# controller.net
KiCad netlist of a schematic drawn in Altium Designer
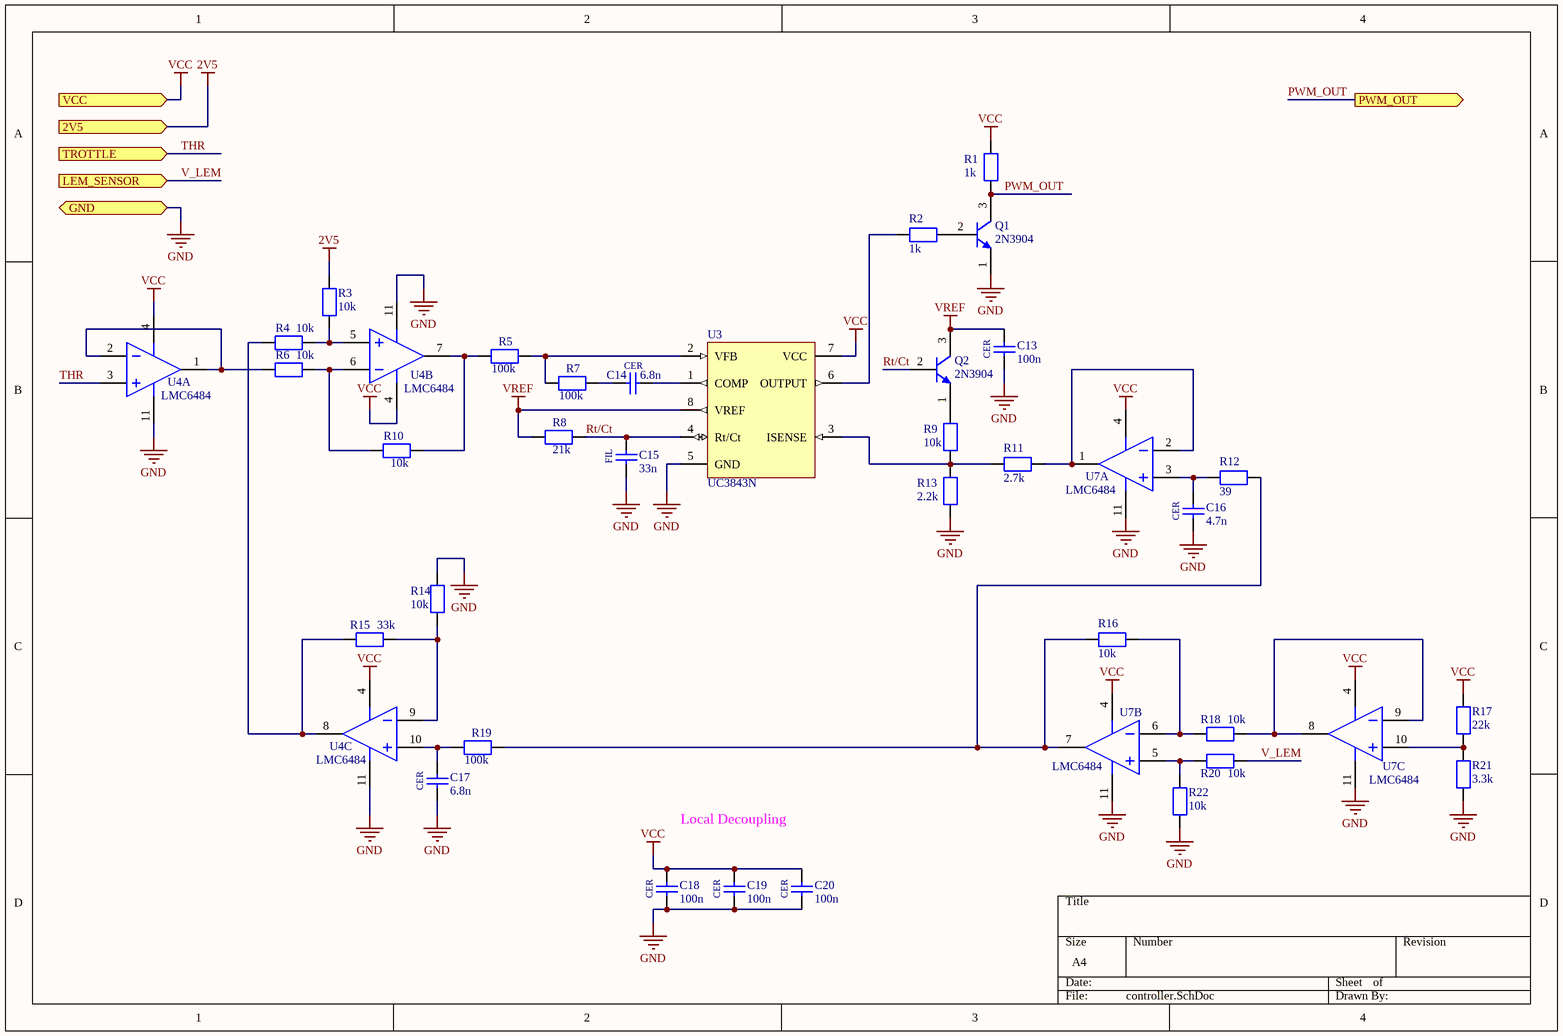
[diagram p0: controller.SchDoc]

(export (version "E")
  (design (tool "Eeschema 10.0.6"))
  (components
    (comp (ref "C13") (value "100n") (footprint "CAP_CER_2.50") (libsource (lib "go_kart") (part "CAP_CER")))
    (comp (ref "C14") (value "6.8n") (footprint "CAP_CER_2.50") (libsource (lib "go_kart") (part "CAP_CER")))
    (comp (ref "C15") (value "33n") (footprint "CAP_FILM_10.0") (libsource (lib "go_kart") (part "CAP_FILM")))
    (comp (ref "C16") (value "4.7n") (footprint "CAP_CER_2.50") (libsource (lib "go_kart") (part "CAP_CER")))
    (comp (ref "C17") (value "6.8n") (footprint "CAP_CER_2.50") (libsource (lib "go_kart") (part "CAP_CER")))
    (comp (ref "C18") (value "100n") (footprint "CAP_CER_2.50") (libsource (lib "go_kart") (part "CAP_CER")))
    (comp (ref "C19") (value "100n") (footprint "CAP_CER_2.50") (libsource (lib "go_kart") (part "CAP_CER")))
    (comp (ref "C20") (value "100n") (footprint "CAP_CER_2.50") (libsource (lib "go_kart") (part "CAP_CER")))
    (comp (ref "Q1")
      (value "2N3904")
      (footprint "ONSC-TO-92-3-29-04_AD")
      (libsource (lib "go_kart") (part "2N3904"))
    )
    (comp (ref "Q2")
      (value "2N3904")
      (footprint "ONSC-TO-92-3-29-04_AD")
      (libsource (lib "go_kart") (part "2N3904"))
    )
    (comp (ref "R1")
      (value "1k")
      (footprint "RESISTOR_THROUGH_HOLE")
      (libsource (lib "go_kart") (part "Resistor"))
    )
    (comp (ref "R2")
      (value "1k")
      (footprint "RESISTOR_THROUGH_HOLE")
      (libsource (lib "go_kart") (part "Resistor"))
    )
    (comp (ref "R3")
      (value "10k")
      (footprint "RESISTOR_THROUGH_HOLE")
      (libsource (lib "go_kart") (part "Resistor"))
    )
    (comp (ref "R4")
      (value "10k")
      (footprint "RESISTOR_THROUGH_HOLE")
      (libsource (lib "go_kart") (part "Resistor"))
    )
    (comp (ref "R5")
      (value "100k")
      (footprint "RESISTOR_THROUGH_HOLE")
      (libsource (lib "go_kart") (part "Resistor"))
    )
    (comp (ref "R6")
      (value "10k")
      (footprint "RESISTOR_THROUGH_HOLE")
      (libsource (lib "go_kart") (part "Resistor"))
    )
    (comp (ref "R7")
      (value "100k")
      (footprint "RESISTOR_THROUGH_HOLE")
      (libsource (lib "go_kart") (part "Resistor"))
    )
    (comp (ref "R8")
      (value "21k")
      (footprint "RESISTOR_THROUGH_HOLE")
      (libsource (lib "go_kart") (part "Resistor"))
    )
    (comp (ref "R9")
      (value "10k")
      (footprint "RESISTOR_THROUGH_HOLE")
      (libsource (lib "go_kart") (part "Resistor"))
    )
    (comp (ref "R10")
      (value "10k")
      (footprint "RESISTOR_THROUGH_HOLE")
      (libsource (lib "go_kart") (part "Resistor"))
    )
    (comp (ref "R11")
      (value "2.7k")
      (footprint "RESISTOR_THROUGH_HOLE")
      (libsource (lib "go_kart") (part "Resistor"))
    )
    (comp (ref "R12")
      (value "39")
      (footprint "RESISTOR_THROUGH_HOLE")
      (libsource (lib "go_kart") (part "Resistor"))
    )
    (comp (ref "R13")
      (value "2.2k")
      (footprint "RESISTOR_THROUGH_HOLE")
      (libsource (lib "go_kart") (part "Resistor"))
    )
    (comp (ref "R14")
      (value "10k")
      (footprint "RESISTOR_THROUGH_HOLE")
      (libsource (lib "go_kart") (part "Resistor"))
    )
    (comp (ref "R15")
      (value "33k")
      (footprint "RESISTOR_THROUGH_HOLE")
      (libsource (lib "go_kart") (part "Resistor"))
    )
    (comp (ref "R16")
      (value "10k")
      (footprint "RESISTOR_THROUGH_HOLE")
      (libsource (lib "go_kart") (part "Resistor"))
    )
    (comp (ref "R17")
      (value "22k")
      (footprint "RESISTOR_THROUGH_HOLE")
      (libsource (lib "go_kart") (part "Resistor"))
    )
    (comp (ref "R18")
      (value "10k")
      (footprint "RESISTOR_THROUGH_HOLE")
      (libsource (lib "go_kart") (part "Resistor"))
    )
    (comp (ref "R19")
      (value "100k")
      (footprint "RESISTOR_THROUGH_HOLE")
      (libsource (lib "go_kart") (part "Resistor"))
    )
    (comp (ref "R20")
      (value "10k")
      (footprint "RESISTOR_THROUGH_HOLE")
      (libsource (lib "go_kart") (part "Resistor"))
    )
    (comp (ref "R21")
      (value "3.3k")
      (footprint "RESISTOR_THROUGH_HOLE")
      (libsource (lib "go_kart") (part "Resistor"))
    )
    (comp (ref "R22")
      (value "10k")
      (footprint "RESISTOR_THROUGH_HOLE")
      (libsource (lib "go_kart") (part "Resistor"))
    )
    (comp (ref "U3")
      (value "UC3843N")
      (footprint "UC3843N")
      (fields (field (name "MANUFACTURER") "Texas Instruments"))
      (libsource (lib "go_kart") (part "UC3843N"))
    )
    (comp (ref "U4") (value "LMC6484") (footprint "TI-J14") (libsource (lib "go_kart") (part "LMC6484")))
    (comp (ref "U7") (value "LMC6484") (footprint "TI-J14") (libsource (lib "go_kart") (part "LMC6484")))
  )
  (nets
    (net (code "1") (name "/PWM_OUT") (class "Default")
      (node (ref "Q1") (pin "3") (pinfunction "C_3") (pintype "passive"))
      (node (ref "R1") (pin "2") (pinfunction "2_2") (pintype "passive"))
    )
    (net (code "2") (name "/Rt{slash}Ct") (class "Default")
      (node (ref "C15") (pin "2") (pinfunction "2_2") (pintype "passive"))
      (node (ref "Q2") (pin "2") (pinfunction "B_2") (pintype "passive"))
      (node (ref "R8") (pin "2") (pinfunction "2_2") (pintype "passive"))
      (node (ref "U3") (pin "4") (pinfunction "Rt/Ct_4") (pintype "bidirectional"))
    )
    (net (code "3") (name "/THR") (class "Default")
      (node (ref "U4") (pin "3") (pinfunction "IN1+_3") (pintype "passive"))
    )
    (net (code "4") (name "/V_LEM") (class "Default")
      (node (ref "R20") (pin "2") (pinfunction "2_2") (pintype "passive"))
    )
    (net (code "5") (name "2V5") (class "Default")
      (node (ref "R3") (pin "1") (pinfunction "1_1") (pintype "passive"))
    )
    (net (code "6") (name "GND") (class "Default")
      (node (ref "C13") (pin "1") (pinfunction "1_1") (pintype "passive"))
      (node (ref "C15") (pin "1") (pinfunction "1_1") (pintype "passive"))
      (node (ref "C16") (pin "1") (pinfunction "1_1") (pintype "passive"))
      (node (ref "C17") (pin "1") (pinfunction "1_1") (pintype "passive"))
      (node (ref "C18") (pin "1") (pinfunction "1_1") (pintype "passive"))
      (node (ref "C19") (pin "1") (pinfunction "1_1") (pintype "passive"))
      (node (ref "C20") (pin "1") (pinfunction "1_1") (pintype "passive"))
      (node (ref "Q1") (pin "1") (pinfunction "E_1") (pintype "passive"))
      (node (ref "R13") (pin "2") (pinfunction "2_2") (pintype "passive"))
      (node (ref "R14") (pin "1") (pinfunction "1_1") (pintype "passive"))
      (node (ref "R21") (pin "1") (pinfunction "1_1") (pintype "passive"))
      (node (ref "R22") (pin "1") (pinfunction "1_1") (pintype "passive"))
      (node (ref "U3") (pin "5") (pinfunction "GND_5") (pintype "passive"))
      (node (ref "U4") (pin "11") (pinfunction "VCC-_11") (pintype "passive"))
      (node (ref "U7") (pin "11") (pinfunction "VCC-_11") (pintype "passive"))
    )
    (net (code "7") (name "Net-(C14-Pad1)") (class "Default")
      (node (ref "C14") (pin "1") (pinfunction "1_1") (pintype "passive"))
      (node (ref "R7") (pin "2") (pinfunction "2_2") (pintype "passive"))
    )
    (net (code "8") (name "Net-(Q1-B)") (class "Default")
      (node (ref "Q1") (pin "2") (pinfunction "B_2") (pintype "passive"))
      (node (ref "R2") (pin "2") (pinfunction "2_2") (pintype "passive"))
    )
    (net (code "9") (name "Net-(Q2-E)") (class "Default")
      (node (ref "Q2") (pin "1") (pinfunction "E_1") (pintype "passive"))
      (node (ref "R9") (pin "1") (pinfunction "1_1") (pintype "passive"))
    )
    (net (code "10") (name "Net-(U3-COMP)") (class "Default")
      (node (ref "C14") (pin "2") (pinfunction "2_2") (pintype "passive"))
      (node (ref "U3") (pin "1") (pinfunction "COMP_1") (pintype "output"))
    )
    (net (code "11") (name "Net-(U3-ISENSE)") (class "Default")
      (node (ref "R11") (pin "1") (pinfunction "1_1") (pintype "passive"))
      (node (ref "R13") (pin "1") (pinfunction "1_1") (pintype "passive"))
      (node (ref "R9") (pin "2") (pinfunction "2_2") (pintype "passive"))
      (node (ref "U3") (pin "3") (pinfunction "ISENSE_3") (pintype "input"))
    )
    (net (code "12") (name "Net-(U3-OUTPUT)") (class "Default")
      (node (ref "R2") (pin "1") (pinfunction "1_1") (pintype "passive"))
      (node (ref "U3") (pin "6") (pinfunction "OUTPUT_6") (pintype "output"))
    )
    (net (code "13") (name "Net-(U3-VFB)") (class "Default")
      (node (ref "R5") (pin "2") (pinfunction "2_2") (pintype "passive"))
      (node (ref "R7") (pin "1") (pinfunction "1_1") (pintype "passive"))
      (node (ref "U3") (pin "2") (pinfunction "VFB_2") (pintype "input"))
    )
    (net (code "14") (name "Net-(U4A-IN1-)") (class "Default")
      (node (ref "R6") (pin "2") (pinfunction "2_2") (pintype "passive"))
      (node (ref "U4") (pin "1") (pinfunction "OUT1_1") (pintype "passive"))
      (node (ref "U4") (pin "2") (pinfunction "IN1-_2") (pintype "passive"))
    )
    (net (code "15") (name "Net-(U4B-IN2+)") (class "Default")
      (node (ref "R3") (pin "2") (pinfunction "2_2") (pintype "passive"))
      (node (ref "R4") (pin "2") (pinfunction "2_2") (pintype "passive"))
      (node (ref "U4") (pin "5") (pinfunction "IN2+_5") (pintype "passive"))
    )
    (net (code "16") (name "Net-(U4B-IN2-)") (class "Default")
      (node (ref "R10") (pin "2") (pinfunction "2_2") (pintype "passive"))
      (node (ref "R6") (pin "1") (pinfunction "1_1") (pintype "passive"))
      (node (ref "U4") (pin "6") (pinfunction "IN2-_6") (pintype "passive"))
    )
    (net (code "17") (name "Net-(U4B-OUT2)") (class "Default")
      (node (ref "R10") (pin "1") (pinfunction "1_1") (pintype "passive"))
      (node (ref "R5") (pin "1") (pinfunction "1_1") (pintype "passive"))
      (node (ref "U4") (pin "7") (pinfunction "OUT2_7") (pintype "passive"))
    )
    (net (code "18") (name "Net-(U4C-IN3+)") (class "Default")
      (node (ref "C17") (pin "2") (pinfunction "2_2") (pintype "passive"))
      (node (ref "R19") (pin "2") (pinfunction "2_2") (pintype "passive"))
      (node (ref "U4") (pin "10") (pinfunction "IN3+_10") (pintype "passive"))
    )
    (net (code "19") (name "Net-(U4C-IN3-)") (class "Default")
      (node (ref "R14") (pin "2") (pinfunction "2_2") (pintype "passive"))
      (node (ref "R15") (pin "2") (pinfunction "2_2") (pintype "passive"))
      (node (ref "U4") (pin "9") (pinfunction "IN3-_9") (pintype "passive"))
    )
    (net (code "20") (name "Net-(U4C-OUT3)") (class "Default")
      (node (ref "R15") (pin "1") (pinfunction "1_1") (pintype "passive"))
      (node (ref "R4") (pin "1") (pinfunction "1_1") (pintype "passive"))
      (node (ref "U4") (pin "8") (pinfunction "OUT3_8") (pintype "passive"))
    )
    (net (code "21") (name "Net-(U7A-IN1+)") (class "Default")
      (node (ref "C16") (pin "2") (pinfunction "2_2") (pintype "passive"))
      (node (ref "R12") (pin "1") (pinfunction "1_1") (pintype "passive"))
      (node (ref "U7") (pin "3") (pinfunction "IN1+_3") (pintype "passive"))
    )
    (net (code "22") (name "Net-(U7A-IN1-)") (class "Default")
      (node (ref "R11") (pin "2") (pinfunction "2_2") (pintype "passive"))
      (node (ref "U7") (pin "1") (pinfunction "OUT1_1") (pintype "passive"))
      (node (ref "U7") (pin "2") (pinfunction "IN1-_2") (pintype "passive"))
    )
    (net (code "23") (name "Net-(U7B-IN2+)") (class "Default")
      (node (ref "R20") (pin "1") (pinfunction "1_1") (pintype "passive"))
      (node (ref "R22") (pin "2") (pinfunction "2_2") (pintype "passive"))
      (node (ref "U7") (pin "5") (pinfunction "IN2+_5") (pintype "passive"))
    )
    (net (code "24") (name "Net-(U7B-IN2-)") (class "Default")
      (node (ref "R16") (pin "2") (pinfunction "2_2") (pintype "passive"))
      (node (ref "R18") (pin "1") (pinfunction "1_1") (pintype "passive"))
      (node (ref "U7") (pin "6") (pinfunction "IN2-_6") (pintype "passive"))
    )
    (net (code "25") (name "Net-(U7B-OUT2)") (class "Default")
      (node (ref "R12") (pin "2") (pinfunction "2_2") (pintype "passive"))
      (node (ref "R16") (pin "1") (pinfunction "1_1") (pintype "passive"))
      (node (ref "R19") (pin "1") (pinfunction "1_1") (pintype "passive"))
      (node (ref "U7") (pin "7") (pinfunction "OUT2_7") (pintype "passive"))
    )
    (net (code "26") (name "Net-(U7C-IN3+)") (class "Default")
      (node (ref "R17") (pin "1") (pinfunction "1_1") (pintype "passive"))
      (node (ref "R21") (pin "2") (pinfunction "2_2") (pintype "passive"))
      (node (ref "U7") (pin "10") (pinfunction "IN3+_10") (pintype "passive"))
    )
    (net (code "27") (name "Net-(U7C-IN3-)") (class "Default")
      (node (ref "R18") (pin "2") (pinfunction "2_2") (pintype "passive"))
      (node (ref "U7") (pin "8") (pinfunction "OUT3_8") (pintype "passive"))
      (node (ref "U7") (pin "9") (pinfunction "IN3-_9") (pintype "passive"))
    )
    (net (code "28") (name "VCC") (class "Default")
      (node (ref "C18") (pin "2") (pinfunction "2_2") (pintype "passive"))
      (node (ref "C19") (pin "2") (pinfunction "2_2") (pintype "passive"))
      (node (ref "C20") (pin "2") (pinfunction "2_2") (pintype "passive"))
      (node (ref "R1") (pin "1") (pinfunction "1_1") (pintype "passive"))
      (node (ref "R17") (pin "2") (pinfunction "2_2") (pintype "passive"))
      (node (ref "U3") (pin "7") (pinfunction "VCC_7") (pintype "passive"))
      (node (ref "U4") (pin "4") (pinfunction "VCC+_4") (pintype "passive"))
      (node (ref "U7") (pin "4") (pinfunction "VCC+_4") (pintype "passive"))
    )
    (net (code "29") (name "VREF") (class "Default")
      (node (ref "C13") (pin "2") (pinfunction "2_2") (pintype "passive"))
      (node (ref "Q2") (pin "3") (pinfunction "C_3") (pintype "passive"))
      (node (ref "R8") (pin "1") (pinfunction "1_1") (pintype "passive"))
      (node (ref "U3") (pin "8") (pinfunction "VREF_8") (pintype "output"))
    )
  )
)
